# Programmer.net
KiCad netlist of a schematic drawn in EAGLE
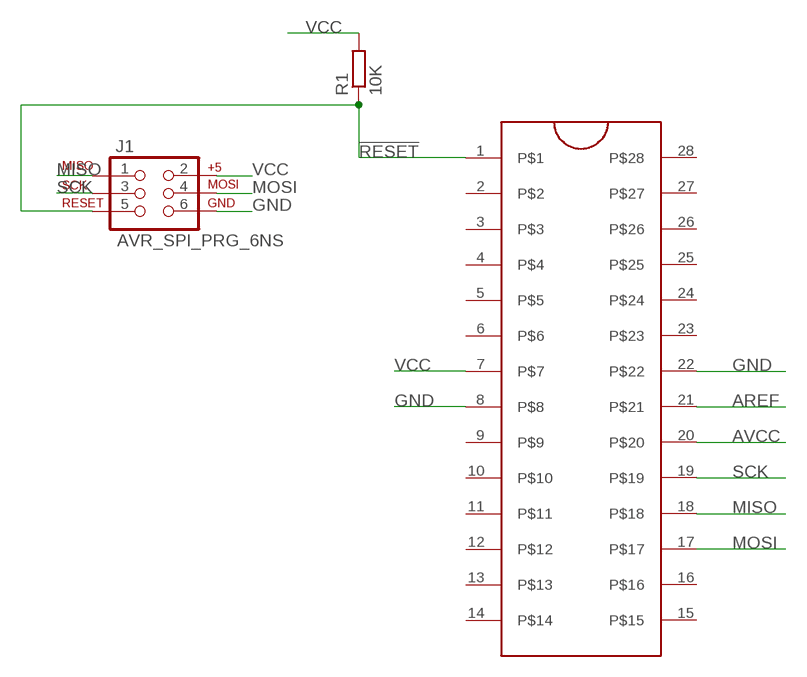
[diagram p0: schematic, sheet 1]

(export (version "E")
  (design (tool "Eeschema 10.0.6"))
  (components
    (comp (ref "J1")
      (value "AVR_SPI_PRG_6NS")
      (footprint "eagle-import:2X3-NS")
      (libsource (lib "eagle-import") (part "AVR_SPI_PRG_6NS"))
    )
    (comp (ref "R1")
      (value "10K")
      (footprint "eagle-import:0207_10")
      (libsource (lib "eagle-import") (part "R-EU_0207/10"))
    )
    (comp (ref "U$1")
      (value "ZIFSOCKET-28-3ZIFFSOCKET-28-3")
      (footprint "eagle-import:DIL28-3-ZIF_SOCKET")
      (libsource (lib "eagle-import") (part "ZIFSOCKET-28-3ZIFFSOCKET-28-3"))
    )
  )
  (nets
    (net (code "1") (name "/AREF") (class "Default")
      (node (ref "U$1") (pin "21") (pinfunction "P$21_21") (pintype "bidirectional"))
    )
    (net (code "2") (name "/AVCC") (class "Default")
      (node (ref "U$1") (pin "20") (pinfunction "P$20_20") (pintype "bidirectional"))
    )
    (net (code "3") (name "/GND") (class "Default")
      (node (ref "J1") (pin "6") (pinfunction "6_6") (pintype "passive"))
      (node (ref "U$1") (pin "22") (pinfunction "P$22_22") (pintype "bidirectional"))
      (node (ref "U$1") (pin "8") (pinfunction "P$8_8") (pintype "bidirectional"))
    )
    (net (code "4") (name "/MISO") (class "Default")
      (node (ref "J1") (pin "1") (pinfunction "1_1") (pintype "passive"))
      (node (ref "U$1") (pin "18") (pinfunction "P$18_18") (pintype "bidirectional"))
    )
    (net (code "5") (name "/MOSI") (class "Default")
      (node (ref "J1") (pin "4") (pinfunction "4_4") (pintype "passive"))
      (node (ref "U$1") (pin "17") (pinfunction "P$17_17") (pintype "bidirectional"))
    )
    (net (code "6") (name "/SCK") (class "Default")
      (node (ref "J1") (pin "3") (pinfunction "3_3") (pintype "passive"))
      (node (ref "U$1") (pin "19") (pinfunction "P$19_19") (pintype "bidirectional"))
    )
    (net (code "7") (name "/VCC") (class "Default")
      (node (ref "J1") (pin "2") (pinfunction "2_2") (pintype "passive"))
      (node (ref "R1") (pin "2") (pinfunction "2_2") (pintype "passive"))
      (node (ref "U$1") (pin "7") (pinfunction "P$7_7") (pintype "bidirectional"))
    )
    (net (code "8") (name "/~{RESET}") (class "Default")
      (node (ref "J1") (pin "5") (pinfunction "5_5") (pintype "passive"))
      (node (ref "R1") (pin "1") (pinfunction "1_1") (pintype "passive"))
      (node (ref "U$1") (pin "1") (pinfunction "P$1_1") (pintype "bidirectional"))
    )
    (net (code "9") (name "unconnected-(U$1-P$2-Pad2)") (class "Default")
      (node (ref "U$1") (pin "2") (pinfunction "P$2_2") (pintype "bidirectional"))
    )
    (net (code "10") (name "unconnected-(U$1-P$3-Pad3)") (class "Default")
      (node (ref "U$1") (pin "3") (pinfunction "P$3_3") (pintype "bidirectional"))
    )
    (net (code "11") (name "unconnected-(U$1-P$4-Pad4)") (class "Default")
      (node (ref "U$1") (pin "4") (pinfunction "P$4_4") (pintype "bidirectional"))
    )
    (net (code "12") (name "unconnected-(U$1-P$5-Pad5)") (class "Default")
      (node (ref "U$1") (pin "5") (pinfunction "P$5_5") (pintype "bidirectional"))
    )
    (net (code "13") (name "unconnected-(U$1-P$6-Pad6)") (class "Default")
      (node (ref "U$1") (pin "6") (pinfunction "P$6_6") (pintype "bidirectional"))
    )
    (net (code "14") (name "unconnected-(U$1-P$9-Pad9)") (class "Default")
      (node (ref "U$1") (pin "9") (pinfunction "P$9_9") (pintype "bidirectional"))
    )
    (net (code "15") (name "unconnected-(U$1-P$10-Pad10)") (class "Default")
      (node (ref "U$1") (pin "10") (pinfunction "P$10_10") (pintype "bidirectional"))
    )
    (net (code "16") (name "unconnected-(U$1-P$11-Pad11)") (class "Default")
      (node (ref "U$1") (pin "11") (pinfunction "P$11_11") (pintype "bidirectional"))
    )
    (net (code "17") (name "unconnected-(U$1-P$12-Pad12)") (class "Default")
      (node (ref "U$1") (pin "12") (pinfunction "P$12_12") (pintype "bidirectional"))
    )
    (net (code "18") (name "unconnected-(U$1-P$13-Pad13)") (class "Default")
      (node (ref "U$1") (pin "13") (pinfunction "P$13_13") (pintype "bidirectional"))
    )
    (net (code "19") (name "unconnected-(U$1-P$14-Pad14)") (class "Default")
      (node (ref "U$1") (pin "14") (pinfunction "P$14_14") (pintype "bidirectional"))
    )
    (net (code "20") (name "unconnected-(U$1-P$15-Pad15)") (class "Default")
      (node (ref "U$1") (pin "15") (pinfunction "P$15_15") (pintype "bidirectional"))
    )
    (net (code "21") (name "unconnected-(U$1-P$16-Pad16)") (class "Default")
      (node (ref "U$1") (pin "16") (pinfunction "P$16_16") (pintype "bidirectional"))
    )
    (net (code "22") (name "unconnected-(U$1-P$23-Pad23)") (class "Default")
      (node (ref "U$1") (pin "23") (pinfunction "P$23_23") (pintype "bidirectional"))
    )
    (net (code "23") (name "unconnected-(U$1-P$24-Pad24)") (class "Default")
      (node (ref "U$1") (pin "24") (pinfunction "P$24_24") (pintype "bidirectional"))
    )
    (net (code "24") (name "unconnected-(U$1-P$25-Pad25)") (class "Default")
      (node (ref "U$1") (pin "25") (pinfunction "P$25_25") (pintype "bidirectional"))
    )
    (net (code "25") (name "unconnected-(U$1-P$26-Pad26)") (class "Default")
      (node (ref "U$1") (pin "26") (pinfunction "P$26_26") (pintype "bidirectional"))
    )
    (net (code "26") (name "unconnected-(U$1-P$27-Pad27)") (class "Default")
      (node (ref "U$1") (pin "27") (pinfunction "P$27_27") (pintype "bidirectional"))
    )
    (net (code "27") (name "unconnected-(U$1-P$28-Pad28)") (class "Default")
      (node (ref "U$1") (pin "28") (pinfunction "P$28_28") (pintype "bidirectional"))
    )
  )
)
